# thewing_rev0.net
KiCad netlist of a schematic drawn in EAGLE
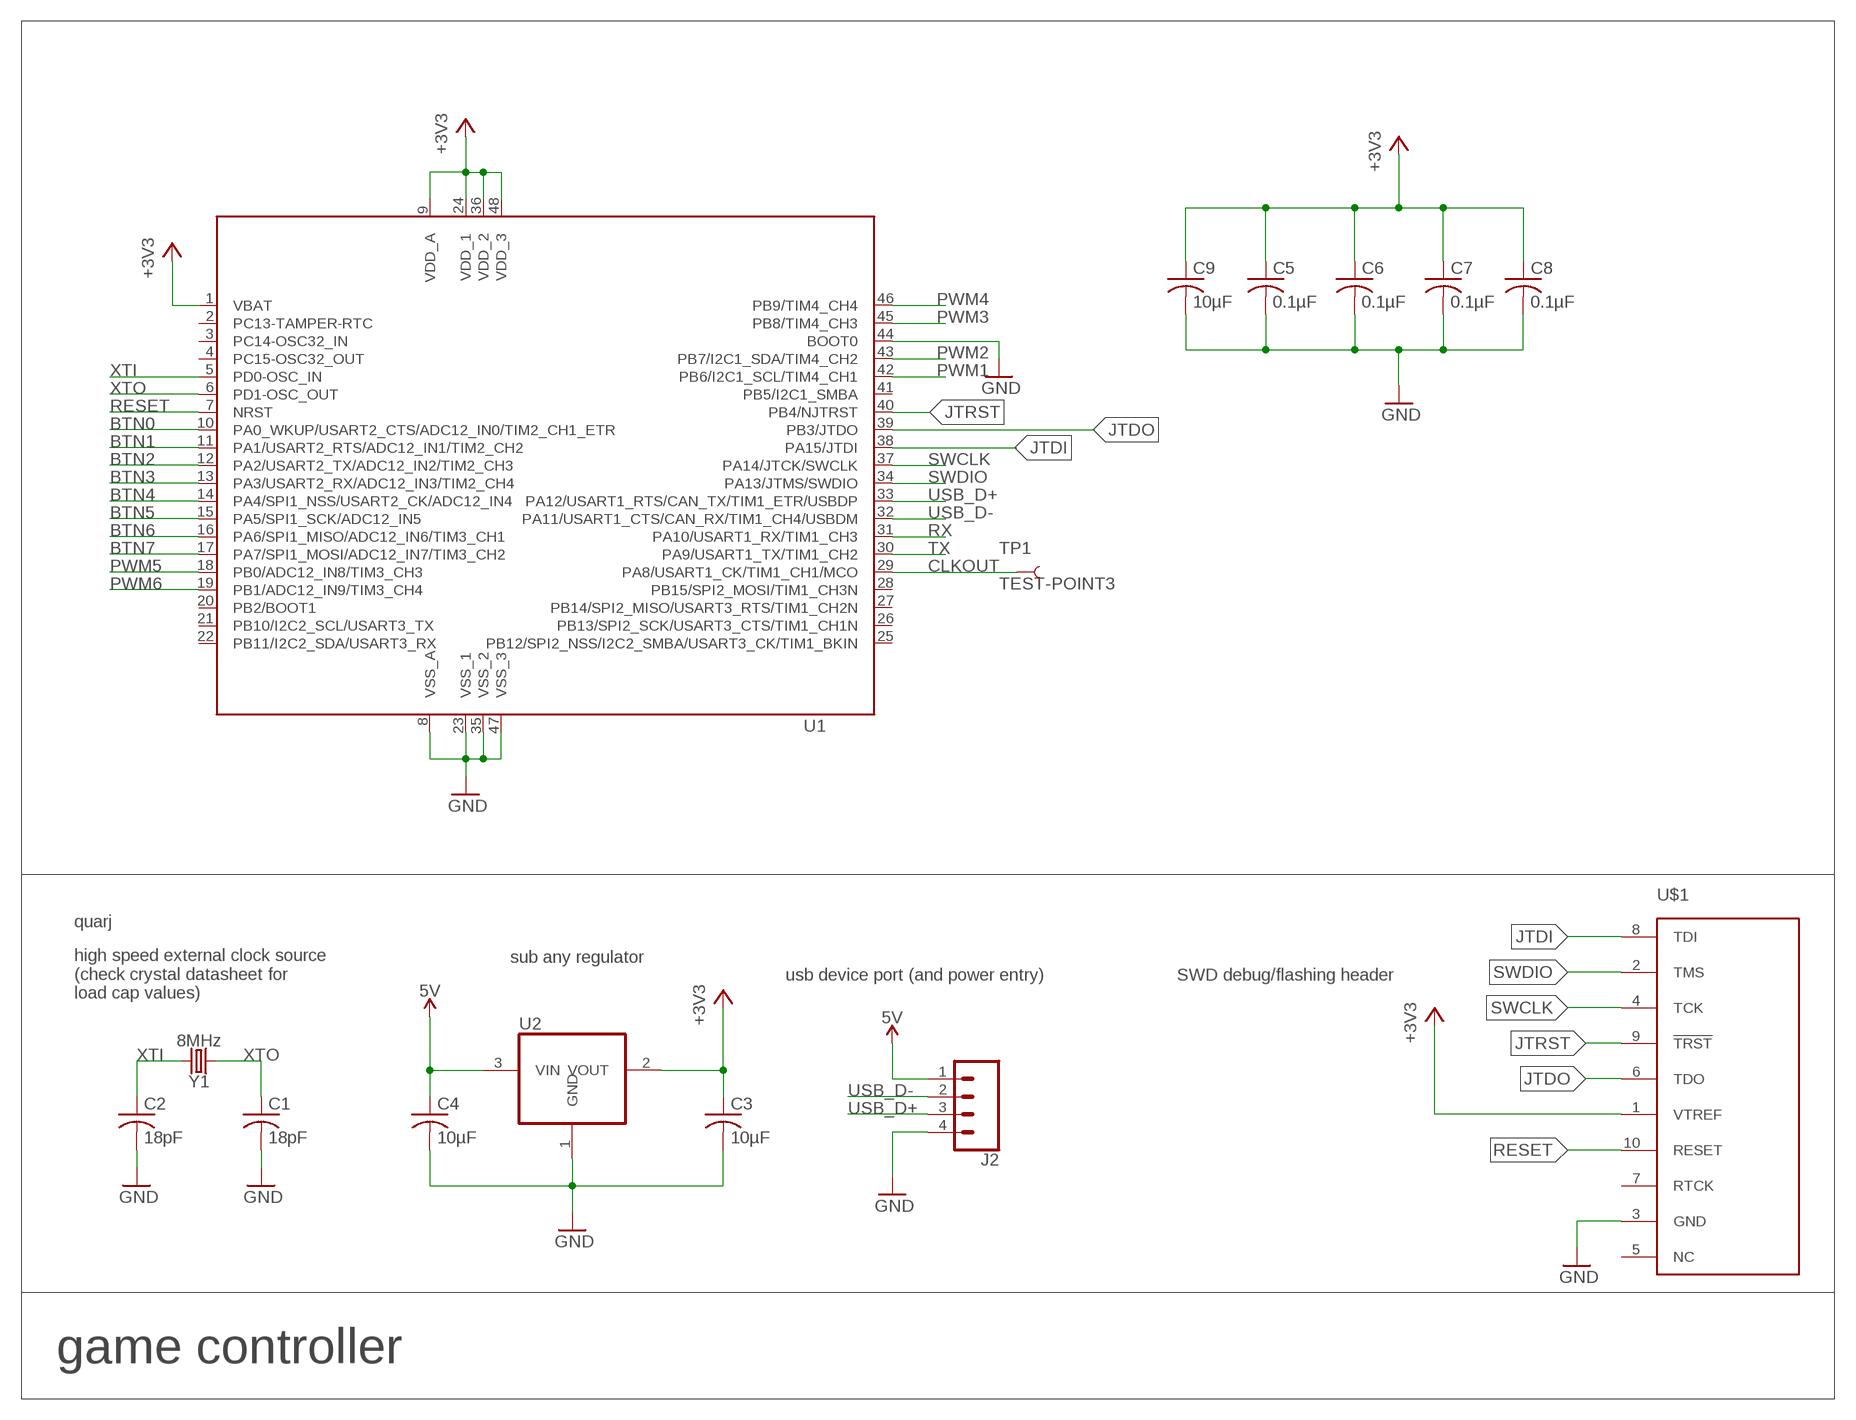
[diagram p0: schematic, sheet 1]
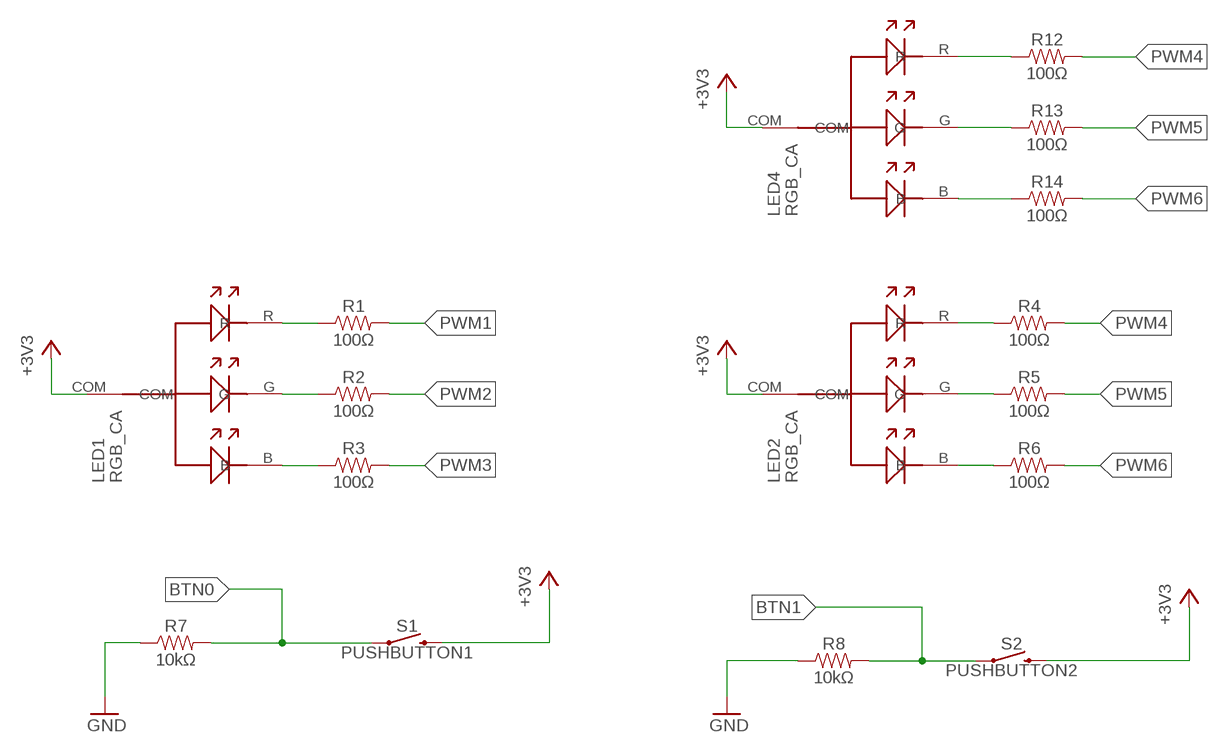
[diagram p1: schematic, sheet 2]
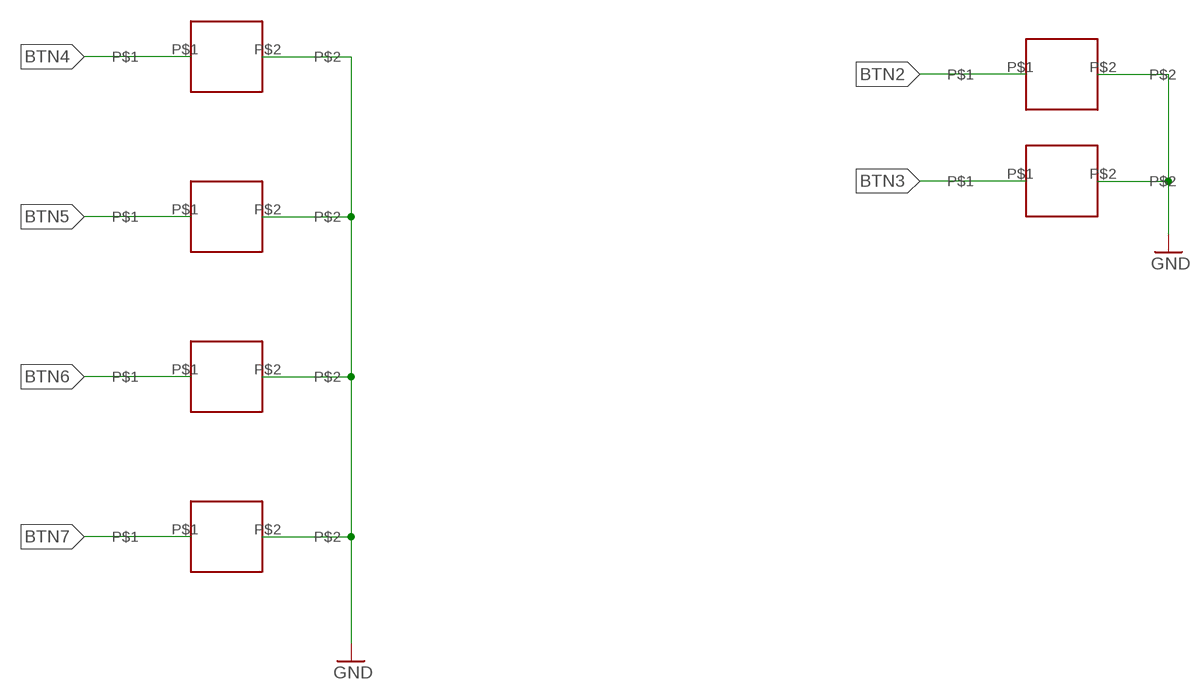
[diagram p2: schematic, sheet 3]

(export (version "E")
  (design (tool "Eeschema 10.0.6"))
  (components
    (comp (ref "A")
      (value "HYPERKIN_TOUCHPAD_CADET")
      (footprint "eagle-import:HYPERKIN_TOUCHPLATE_CADET")
      (libsource (lib "eagle-import") (part "HYPERKIN_TOUCHPAD_CADET"))
    )
    (comp (ref "B")
      (value "HYPERKIN_TOUCHPAD_CADET")
      (footprint "eagle-import:HYPERKIN_TOUCHPLATE_CADET")
      (libsource (lib "eagle-import") (part "HYPERKIN_TOUCHPAD_CADET"))
    )
    (comp (ref "D")
      (value "HYPERKIN_TOUCHPAD_CADET")
      (footprint "eagle-import:HYPERKIN_TOUCHPLATE_CADET")
      (libsource (lib "eagle-import") (part "HYPERKIN_TOUCHPAD_CADET"))
    )
    (comp (ref "L")
      (value "HYPERKIN_TOUCHPAD_CADET")
      (footprint "eagle-import:HYPERKIN_TOUCHPLATE_CADET")
      (libsource (lib "eagle-import") (part "HYPERKIN_TOUCHPAD_CADET"))
    )
    (comp (ref "R")
      (value "HYPERKIN_TOUCHPAD_CADET")
      (footprint "eagle-import:HYPERKIN_TOUCHPLATE_CADET")
      (libsource (lib "eagle-import") (part "HYPERKIN_TOUCHPAD_CADET"))
    )
    (comp (ref "U")
      (value "HYPERKIN_TOUCHPAD_CADET")
      (footprint "eagle-import:HYPERKIN_TOUCHPLATE_CADET")
      (libsource (lib "eagle-import") (part "HYPERKIN_TOUCHPAD_CADET"))
    )
    (comp (ref "C1")
      (value "18pF")
      (footprint "eagle-import:RCL_C0805K")
      (libsource (lib "eagle-import") (part "RCL_C-USC0805K"))
    )
    (comp (ref "C2")
      (value "18pF")
      (footprint "eagle-import:RCL_C0805K")
      (libsource (lib "eagle-import") (part "RCL_C-USC0805K"))
    )
    (comp (ref "C3")
      (value "10µF")
      (footprint "eagle-import:RCL_C0805K")
      (libsource (lib "eagle-import") (part "RCL_C-USC0805K"))
    )
    (comp (ref "C4")
      (value "10µF")
      (footprint "eagle-import:RCL_C0805K")
      (libsource (lib "eagle-import") (part "RCL_C-USC0805K"))
    )
    (comp (ref "C5")
      (value "0.1µF")
      (footprint "eagle-import:RCL_C0805K")
      (libsource (lib "eagle-import") (part "RCL_C-USC0805K"))
    )
    (comp (ref "C6")
      (value "0.1µF")
      (footprint "eagle-import:RCL_C0805K")
      (libsource (lib "eagle-import") (part "RCL_C-USC0805K"))
    )
    (comp (ref "C7")
      (value "0.1µF")
      (footprint "eagle-import:RCL_C0805K")
      (libsource (lib "eagle-import") (part "RCL_C-USC0805K"))
    )
    (comp (ref "C8")
      (value "0.1µF")
      (footprint "eagle-import:RCL_C0805K")
      (libsource (lib "eagle-import") (part "RCL_C-USC0805K"))
    )
    (comp (ref "C9")
      (value "10µF")
      (footprint "eagle-import:RCL_C0805K")
      (libsource (lib "eagle-import") (part "RCL_C-USC0805K"))
    )
    (comp (ref "J2")
      (value "CONN_04")
      (footprint "eagle-import:1X04")
      (libsource (lib "eagle-import") (part "CONN_04"))
    )
    (comp (ref "TP1")
      (value "TEST-POINT3")
      (footprint "eagle-import:PAD.03X.03")
      (libsource (lib "eagle-import") (part "TEST-POINT3"))
    )
    (comp (ref "U$1")
      (value "TC2050-NL-MCP-NL")
      (footprint "eagle-import:TC2030-MCP-NL")
      (libsource (lib "eagle-import") (part "TC2050-NL-MCP-NL"))
    )
    (comp (ref "U1")
      (value "STM32_STM32F102C4")
      (footprint "eagle-import:STM32_LQFP48")
      (libsource (lib "eagle-import") (part "STM32_STM32F102C4"))
    )
    (comp (ref "U2")
      (value "OG-VREG_REG1117")
      (footprint "eagle-import:OG-VREG_SOT223")
      (libsource (lib "eagle-import") (part "OG-VREG_REG1117"))
    )
    (comp (ref "Y1")
      (value "8MHz")
      (footprint "eagle-import:HC49UP")
      (libsource (lib "eagle-import") (part "CRYSTAL-8MHZSMD-HC49UP"))
    )
    (comp (ref "LED1")
      (value "RGB_CA")
      (footprint "eagle-import:RGB_LED_RECTANGULAR_COMMON_ANODE")
      (libsource (lib "eagle-import") (part "RGB_LED_RECTANGULAR_COMMON_ANODE"))
    )
    (comp (ref "LED2")
      (value "RGB_CA")
      (footprint "eagle-import:RGB_LED_RECTANGULAR_COMMON_ANODE")
      (libsource (lib "eagle-import") (part "RGB_LED_RECTANGULAR_COMMON_ANODE"))
    )
    (comp (ref "LED4")
      (value "RGB_CA")
      (footprint "eagle-import:RGB_LED_RECTANGULAR_COMMON_ANODE")
      (libsource (lib "eagle-import") (part "RGB_LED_RECTANGULAR_COMMON_ANODE"))
    )
    (comp (ref "R1")
      (value "100Ω")
      (footprint "eagle-import:0805")
      (libsource (lib "eagle-import") (part "0.3OHM-0805-1/8W-1%"))
    )
    (comp (ref "R2")
      (value "100Ω")
      (footprint "eagle-import:0805")
      (libsource (lib "eagle-import") (part "0.3OHM-0805-1/8W-1%"))
    )
    (comp (ref "R3")
      (value "100Ω")
      (footprint "eagle-import:0805")
      (libsource (lib "eagle-import") (part "0.3OHM-0805-1/8W-1%"))
    )
    (comp (ref "R4")
      (value "100Ω")
      (footprint "eagle-import:0805")
      (libsource (lib "eagle-import") (part "0.3OHM-0805-1/8W-1%"))
    )
    (comp (ref "R5")
      (value "100Ω")
      (footprint "eagle-import:0805")
      (libsource (lib "eagle-import") (part "0.3OHM-0805-1/8W-1%"))
    )
    (comp (ref "R6")
      (value "100Ω")
      (footprint "eagle-import:0805")
      (libsource (lib "eagle-import") (part "0.3OHM-0805-1/8W-1%"))
    )
    (comp (ref "R7")
      (value "10kΩ")
      (footprint "eagle-import:0805")
      (libsource (lib "eagle-import") (part "0.3OHM-0805-1/8W-1%"))
    )
    (comp (ref "R8")
      (value "10kΩ")
      (footprint "eagle-import:0805")
      (libsource (lib "eagle-import") (part "0.3OHM-0805-1/8W-1%"))
    )
    (comp (ref "R12")
      (value "100Ω")
      (footprint "eagle-import:0805")
      (libsource (lib "eagle-import") (part "0.3OHM-0805-1/8W-1%"))
    )
    (comp (ref "R13")
      (value "100Ω")
      (footprint "eagle-import:0805")
      (libsource (lib "eagle-import") (part "0.3OHM-0805-1/8W-1%"))
    )
    (comp (ref "R14")
      (value "100Ω")
      (footprint "eagle-import:0805")
      (libsource (lib "eagle-import") (part "0.3OHM-0805-1/8W-1%"))
    )
    (comp (ref "S1")
      (value "PUSHBUTTON1")
      (footprint "eagle-import:TACTILE_SWITCH_PTH_6.0MM")
      (libsource (lib "eagle-import") (part "MOMENTARY-SWITCH-SPST-PTH-6.0MM"))
    )
    (comp (ref "S2")
      (value "PUSHBUTTON2")
      (footprint "eagle-import:TACTILE_SWITCH_PTH_6.0MM")
      (libsource (lib "eagle-import") (part "MOMENTARY-SWITCH-SPST-PTH-6.0MM"))
    )
  )
  (nets
    (net (code "1") (name "+3V3") (class "Default")
      (node (ref "C3") (pin "1") (pinfunction "1_1") (pintype "passive"))
      (node (ref "C5") (pin "1") (pinfunction "1_1") (pintype "passive"))
      (node (ref "C6") (pin "1") (pinfunction "1_1") (pintype "passive"))
      (node (ref "C7") (pin "1") (pinfunction "1_1") (pintype "passive"))
      (node (ref "C8") (pin "1") (pinfunction "1_1") (pintype "passive"))
      (node (ref "C9") (pin "1") (pinfunction "1_1") (pintype "passive"))
      (node (ref "LED1") (pin "COM") (pinfunction "COM_COM") (pintype "bidirectional"))
      (node (ref "LED2") (pin "COM") (pinfunction "COM_COM") (pintype "bidirectional"))
      (node (ref "LED4") (pin "COM") (pinfunction "COM_COM") (pintype "bidirectional"))
      (node (ref "S1") (pin "3") (pinfunction "2_3") (pintype "passive"))
      (node (ref "S2") (pin "3") (pinfunction "2_3") (pintype "passive"))
      (node (ref "U$1") (pin "1") (pinfunction "VTREF_1") (pintype "bidirectional"))
      (node (ref "U1") (pin "1") (pinfunction "VBAT_1") (pintype "power_in"))
      (node (ref "U1") (pin "24") (pinfunction "VDD_1_24") (pintype "power_in"))
      (node (ref "U1") (pin "36") (pinfunction "VDD_2_36") (pintype "power_in"))
      (node (ref "U1") (pin "48") (pinfunction "VDD_3_48") (pintype "power_in"))
      (node (ref "U1") (pin "9") (pinfunction "VDD_A_9") (pintype "power_in"))
      (node (ref "U2") (pin "2") (pinfunction "VOUT_2") (pintype "output"))
    )
    (net (code "2") (name "5V") (class "Default")
      (node (ref "C4") (pin "1") (pinfunction "1_1") (pintype "passive"))
      (node (ref "J2") (pin "1") (pinfunction "1_1") (pintype "passive"))
      (node (ref "U2") (pin "3") (pinfunction "VIN_3") (pintype "input"))
    )
    (net (code "3") (name "BTN0") (class "Default")
      (node (ref "R7") (pin "2") (pinfunction "2_2") (pintype "passive"))
      (node (ref "S1") (pin "1") (pinfunction "1_1") (pintype "passive"))
      (node (ref "U1") (pin "10") (pinfunction "PA0_WKUP/USART2_CTS/ADC12_IN0/TIM2_CH1_ETR_10") (pintype "bidirectional"))
    )
    (net (code "4") (name "BTN1") (class "Default")
      (node (ref "R8") (pin "2") (pinfunction "2_2") (pintype "passive"))
      (node (ref "S2") (pin "1") (pinfunction "1_1") (pintype "passive"))
      (node (ref "U1") (pin "11") (pinfunction "PA1/USART2_RTS/ADC12_IN1/TIM2_CH2_11") (pintype "bidirectional"))
    )
    (net (code "5") (name "BTN2") (class "Default")
      (node (ref "A") (pin "P$1") (pinfunction "P$1_P$1") (pintype "bidirectional"))
      (node (ref "U1") (pin "12") (pinfunction "PA2/USART2_TX/ADC12_IN2/TIM2_CH3_12") (pintype "bidirectional"))
    )
    (net (code "6") (name "BTN3") (class "Default")
      (node (ref "B") (pin "P$1") (pinfunction "P$1_P$1") (pintype "bidirectional"))
      (node (ref "U1") (pin "13") (pinfunction "PA3/USART2_RX/ADC12_IN3/TIM2_CH4_13") (pintype "bidirectional"))
    )
    (net (code "7") (name "BTN4") (class "Default")
      (node (ref "U") (pin "P$1") (pinfunction "P$1_P$1") (pintype "bidirectional"))
      (node (ref "U1") (pin "14") (pinfunction "PA4/SPI1_NSS/USART2_CK/ADC12_IN4_14") (pintype "bidirectional"))
    )
    (net (code "8") (name "BTN5") (class "Default")
      (node (ref "D") (pin "P$1") (pinfunction "P$1_P$1") (pintype "bidirectional"))
      (node (ref "U1") (pin "15") (pinfunction "PA5/SPI1_SCK/ADC12_IN5_15") (pintype "bidirectional"))
    )
    (net (code "9") (name "BTN6") (class "Default")
      (node (ref "L") (pin "P$1") (pinfunction "P$1_P$1") (pintype "bidirectional"))
      (node (ref "U1") (pin "16") (pinfunction "PA6/SPI1_MISO/ADC12_IN6/TIM3_CH1_16") (pintype "bidirectional"))
    )
    (net (code "10") (name "BTN7") (class "Default")
      (node (ref "R") (pin "P$1") (pinfunction "P$1_P$1") (pintype "bidirectional"))
      (node (ref "U1") (pin "17") (pinfunction "PA7/SPI1_MOSI/ADC12_IN7/TIM3_CH2_17") (pintype "bidirectional"))
    )
    (net (code "11") (name "CLKOUT") (class "Default")
      (node (ref "TP1") (pin "P$1") (pinfunction "1_P$1") (pintype "bidirectional"))
      (node (ref "U1") (pin "29") (pinfunction "PA8/USART1_CK/TIM1_CH1/MCO_29") (pintype "bidirectional"))
    )
    (net (code "12") (name "GND") (class "Default")
      (node (ref "A") (pin "P$2") (pinfunction "P$2_P$2") (pintype "bidirectional"))
      (node (ref "B") (pin "P$2") (pinfunction "P$2_P$2") (pintype "bidirectional"))
      (node (ref "C1") (pin "2") (pinfunction "2_2") (pintype "passive"))
      (node (ref "C2") (pin "2") (pinfunction "2_2") (pintype "passive"))
      (node (ref "C3") (pin "2") (pinfunction "2_2") (pintype "passive"))
      (node (ref "C4") (pin "2") (pinfunction "2_2") (pintype "passive"))
      (node (ref "C5") (pin "2") (pinfunction "2_2") (pintype "passive"))
      (node (ref "C6") (pin "2") (pinfunction "2_2") (pintype "passive"))
      (node (ref "C7") (pin "2") (pinfunction "2_2") (pintype "passive"))
      (node (ref "C8") (pin "2") (pinfunction "2_2") (pintype "passive"))
      (node (ref "C9") (pin "2") (pinfunction "2_2") (pintype "passive"))
      (node (ref "D") (pin "P$2") (pinfunction "P$2_P$2") (pintype "bidirectional"))
      (node (ref "J2") (pin "4") (pinfunction "4_4") (pintype "passive"))
      (node (ref "L") (pin "P$2") (pinfunction "P$2_P$2") (pintype "bidirectional"))
      (node (ref "R") (pin "P$2") (pinfunction "P$2_P$2") (pintype "bidirectional"))
      (node (ref "R7") (pin "1") (pinfunction "1_1") (pintype "passive"))
      (node (ref "R8") (pin "1") (pinfunction "1_1") (pintype "passive"))
      (node (ref "U") (pin "P$2") (pinfunction "P$2_P$2") (pintype "bidirectional"))
      (node (ref "U$1") (pin "3") (pinfunction "GND_3") (pintype "bidirectional"))
      (node (ref "U1") (pin "23") (pinfunction "VSS_1_23") (pintype "power_in"))
      (node (ref "U1") (pin "35") (pinfunction "VSS_2_35") (pintype "power_in"))
      (node (ref "U1") (pin "44") (pinfunction "BOOT0_44") (pintype "input"))
      (node (ref "U1") (pin "47") (pinfunction "VSS_3_47") (pintype "power_in"))
      (node (ref "U1") (pin "8") (pinfunction "VSS_A_8") (pintype "power_in"))
      (node (ref "U2") (pin "1") (pinfunction "GND_1") (pintype "power_in"))
    )
    (net (code "13") (name "JTDI") (class "Default")
      (node (ref "U$1") (pin "8") (pinfunction "TDI_8") (pintype "bidirectional"))
      (node (ref "U1") (pin "38") (pinfunction "PA15/JTDI_38") (pintype "bidirectional"))
    )
    (net (code "14") (name "JTDO") (class "Default")
      (node (ref "U$1") (pin "6") (pinfunction "TDO_6") (pintype "bidirectional"))
      (node (ref "U1") (pin "39") (pinfunction "PB3/JTDO_39") (pintype "bidirectional"))
    )
    (net (code "15") (name "JTRST") (class "Default")
      (node (ref "U$1") (pin "9") (pinfunction "~{TRST}_9") (pintype "bidirectional"))
      (node (ref "U1") (pin "40") (pinfunction "PB4/NJTRST_40") (pintype "bidirectional"))
    )
    (net (code "16") (name "Net-(LED1-PadB)") (class "Default")
      (node (ref "LED1") (pin "B") (pinfunction "B_B") (pintype "bidirectional"))
      (node (ref "R3") (pin "1") (pinfunction "1_1") (pintype "passive"))
    )
    (net (code "17") (name "Net-(LED1-PadG)") (class "Default")
      (node (ref "LED1") (pin "G") (pinfunction "G_G") (pintype "bidirectional"))
      (node (ref "R2") (pin "1") (pinfunction "1_1") (pintype "passive"))
    )
    (net (code "18") (name "Net-(LED1-PadR)") (class "Default")
      (node (ref "LED1") (pin "R") (pinfunction "R_R") (pintype "bidirectional"))
      (node (ref "R1") (pin "1") (pinfunction "1_1") (pintype "passive"))
    )
    (net (code "19") (name "Net-(LED2-PadB)") (class "Default")
      (node (ref "LED2") (pin "B") (pinfunction "B_B") (pintype "bidirectional"))
      (node (ref "R6") (pin "1") (pinfunction "1_1") (pintype "passive"))
    )
    (net (code "20") (name "Net-(LED2-PadG)") (class "Default")
      (node (ref "LED2") (pin "G") (pinfunction "G_G") (pintype "bidirectional"))
      (node (ref "R5") (pin "1") (pinfunction "1_1") (pintype "passive"))
    )
    (net (code "21") (name "Net-(LED2-PadR)") (class "Default")
      (node (ref "LED2") (pin "R") (pinfunction "R_R") (pintype "bidirectional"))
      (node (ref "R4") (pin "1") (pinfunction "1_1") (pintype "passive"))
    )
    (net (code "22") (name "Net-(LED4-PadB)") (class "Default")
      (node (ref "LED4") (pin "B") (pinfunction "B_B") (pintype "bidirectional"))
      (node (ref "R14") (pin "1") (pinfunction "1_1") (pintype "passive"))
    )
    (net (code "23") (name "Net-(LED4-PadG)") (class "Default")
      (node (ref "LED4") (pin "G") (pinfunction "G_G") (pintype "bidirectional"))
      (node (ref "R13") (pin "1") (pinfunction "1_1") (pintype "passive"))
    )
    (net (code "24") (name "Net-(LED4-PadR)") (class "Default")
      (node (ref "LED4") (pin "R") (pinfunction "R_R") (pintype "bidirectional"))
      (node (ref "R12") (pin "1") (pinfunction "1_1") (pintype "passive"))
    )
    (net (code "25") (name "PWM1") (class "Default")
      (node (ref "R1") (pin "2") (pinfunction "2_2") (pintype "passive"))
      (node (ref "U1") (pin "42") (pinfunction "PB6/I2C1_SCL/TIM4_CH1_42") (pintype "input"))
    )
    (net (code "26") (name "PWM2") (class "Default")
      (node (ref "R2") (pin "2") (pinfunction "2_2") (pintype "passive"))
      (node (ref "U1") (pin "43") (pinfunction "PB7/I2C1_SDA/TIM4_CH2_43") (pintype "bidirectional"))
    )
    (net (code "27") (name "PWM3") (class "Default")
      (node (ref "R3") (pin "2") (pinfunction "2_2") (pintype "passive"))
      (node (ref "U1") (pin "45") (pinfunction "PB8/TIM4_CH3_45") (pintype "bidirectional"))
    )
    (net (code "28") (name "PWM4") (class "Default")
      (node (ref "R12") (pin "2") (pinfunction "2_2") (pintype "passive"))
      (node (ref "R4") (pin "2") (pinfunction "2_2") (pintype "passive"))
      (node (ref "U1") (pin "46") (pinfunction "PB9/TIM4_CH4_46") (pintype "input"))
    )
    (net (code "29") (name "PWM5") (class "Default")
      (node (ref "R13") (pin "2") (pinfunction "2_2") (pintype "passive"))
      (node (ref "R5") (pin "2") (pinfunction "2_2") (pintype "passive"))
      (node (ref "U1") (pin "18") (pinfunction "PB0/ADC12_IN8/TIM3_CH3_18") (pintype "bidirectional"))
    )
    (net (code "30") (name "PWM6") (class "Default")
      (node (ref "R14") (pin "2") (pinfunction "2_2") (pintype "passive"))
      (node (ref "R6") (pin "2") (pinfunction "2_2") (pintype "passive"))
      (node (ref "U1") (pin "19") (pinfunction "PB1/ADC12_IN9/TIM3_CH4_19") (pintype "bidirectional"))
    )
    (net (code "31") (name "RESET") (class "Default")
      (node (ref "U$1") (pin "10") (pinfunction "RESET_10") (pintype "bidirectional"))
      (node (ref "U1") (pin "7") (pinfunction "NRST_7") (pintype "input"))
    )
    (net (code "32") (name "RX") (class "Default")
      (node (ref "U1") (pin "31") (pinfunction "PA10/USART1_RX/TIM1_CH3_31") (pintype "bidirectional"))
    )
    (net (code "33") (name "SWCLK") (class "Default")
      (node (ref "U$1") (pin "4") (pinfunction "TCK_4") (pintype "bidirectional"))
      (node (ref "U1") (pin "37") (pinfunction "PA14/JTCK/SWCLK_37") (pintype "bidirectional"))
    )
    (net (code "34") (name "SWDIO") (class "Default")
      (node (ref "U$1") (pin "2") (pinfunction "TMS_2") (pintype "bidirectional"))
      (node (ref "U1") (pin "34") (pinfunction "PA13/JTMS/SWDIO_34") (pintype "bidirectional"))
    )
    (net (code "35") (name "TX") (class "Default")
      (node (ref "U1") (pin "30") (pinfunction "PA9/USART1_TX/TIM1_CH2_30") (pintype "input"))
    )
    (net (code "36") (name "USB_D+") (class "Default")
      (node (ref "J2") (pin "3") (pinfunction "3_3") (pintype "passive"))
      (node (ref "U1") (pin "33") (pinfunction "PA12/USART1_RTS/CAN_TX/TIM1_ETR/USBDP_33") (pintype "bidirectional"))
    )
    (net (code "37") (name "USB_D-") (class "Default")
      (node (ref "J2") (pin "2") (pinfunction "2_2") (pintype "passive"))
      (node (ref "U1") (pin "32") (pinfunction "PA11/USART1_CTS/CAN_RX/TIM1_CH4/USBDM_32") (pintype "bidirectional"))
    )
    (net (code "38") (name "XTI") (class "Default")
      (node (ref "C2") (pin "1") (pinfunction "1_1") (pintype "passive"))
      (node (ref "U1") (pin "5") (pinfunction "PD0-OSC_IN_5") (pintype "input"))
      (node (ref "Y1") (pin "2") (pinfunction "2_2") (pintype "passive"))
    )
    (net (code "39") (name "XTO") (class "Default")
      (node (ref "C1") (pin "1") (pinfunction "1_1") (pintype "passive"))
      (node (ref "U1") (pin "6") (pinfunction "PD1-OSC_OUT_6") (pintype "input"))
      (node (ref "Y1") (pin "1") (pinfunction "1_1") (pintype "passive"))
    )
    (net (code "40") (name "unconnected-(U$1-NC-Pad5)") (class "Default")
      (node (ref "U$1") (pin "5") (pinfunction "NC_5") (pintype "bidirectional"))
    )
    (net (code "41") (name "unconnected-(U$1-RTCK-Pad7)") (class "Default")
      (node (ref "U$1") (pin "7") (pinfunction "RTCK_7") (pintype "bidirectional"))
    )
    (net (code "42") (name "unconnected-(U1-PB2{slash}BOOT1-Pad20)") (class "Default")
      (node (ref "U1") (pin "20") (pinfunction "PB2/BOOT1_20") (pintype "bidirectional"))
    )
    (net (code "43") (name "unconnected-(U1-PB5{slash}I2C1_SMBA-Pad41)") (class "Default")
      (node (ref "U1") (pin "41") (pinfunction "PB5/I2C1_SMBA_41") (pintype "input"))
    )
    (net (code "44") (name "unconnected-(U1-PB10{slash}I2C2_SCL{slash}USART3_TX-Pad21)") (class "Default")
      (node (ref "U1") (pin "21") (pinfunction "PB10/I2C2_SCL/USART3_TX_21") (pintype "input"))
    )
    (net (code "45") (name "unconnected-(U1-PB11{slash}I2C2_SDA{slash}USART3_RX-Pad22)") (class "Default")
      (node (ref "U1") (pin "22") (pinfunction "PB11/I2C2_SDA/USART3_RX_22") (pintype "input"))
    )
    (net (code "46") (name "unconnected-(U1-PB12{slash}SPI2_NSS{slash}I2C2_SMBA{slash}USART3_CK{slash}TIM1_BKIN-Pad25)") (class "Default")
      (node (ref "U1") (pin "25") (pinfunction "PB12/SPI2_NSS/I2C2_SMBA/USART3_CK/TIM1_BKIN_25") (pintype "input"))
    )
    (net (code "47") (name "unconnected-(U1-PB13{slash}SPI2_SCK{slash}USART3_CTS{slash}TIM1_CH1N-Pad26)") (class "Default")
      (node (ref "U1") (pin "26") (pinfunction "PB13/SPI2_SCK/USART3_CTS/TIM1_CH1N_26") (pintype "input"))
    )
    (net (code "48") (name "unconnected-(U1-PB14{slash}SPI2_MISO{slash}USART3_RTS{slash}TIM1_CH2N-Pad27)") (class "Default")
      (node (ref "U1") (pin "27") (pinfunction "PB14/SPI2_MISO/USART3_RTS/TIM1_CH2N_27") (pintype "input"))
    )
    (net (code "49") (name "unconnected-(U1-PB15{slash}SPI2_MOSI{slash}TIM1_CH3N-Pad28)") (class "Default")
      (node (ref "U1") (pin "28") (pinfunction "PB15/SPI2_MOSI/TIM1_CH3N_28") (pintype "input"))
    )
    (net (code "50") (name "unconnected-(U1-PC13-TAMPER-RTC-Pad2)") (class "Default")
      (node (ref "U1") (pin "2") (pinfunction "PC13-TAMPER-RTC_2") (pintype "input"))
    )
    (net (code "51") (name "unconnected-(U1-PC14-OSC32_IN-Pad3)") (class "Default")
      (node (ref "U1") (pin "3") (pinfunction "PC14-OSC32_IN_3") (pintype "input"))
    )
    (net (code "52") (name "unconnected-(U1-PC15-OSC32_OUT-Pad4)") (class "Default")
      (node (ref "U1") (pin "4") (pinfunction "PC15-OSC32_OUT_4") (pintype "input"))
    )
  )
)
